# bci02_corrected.net
KiCad netlist of a schematic drawn in Altium Designer
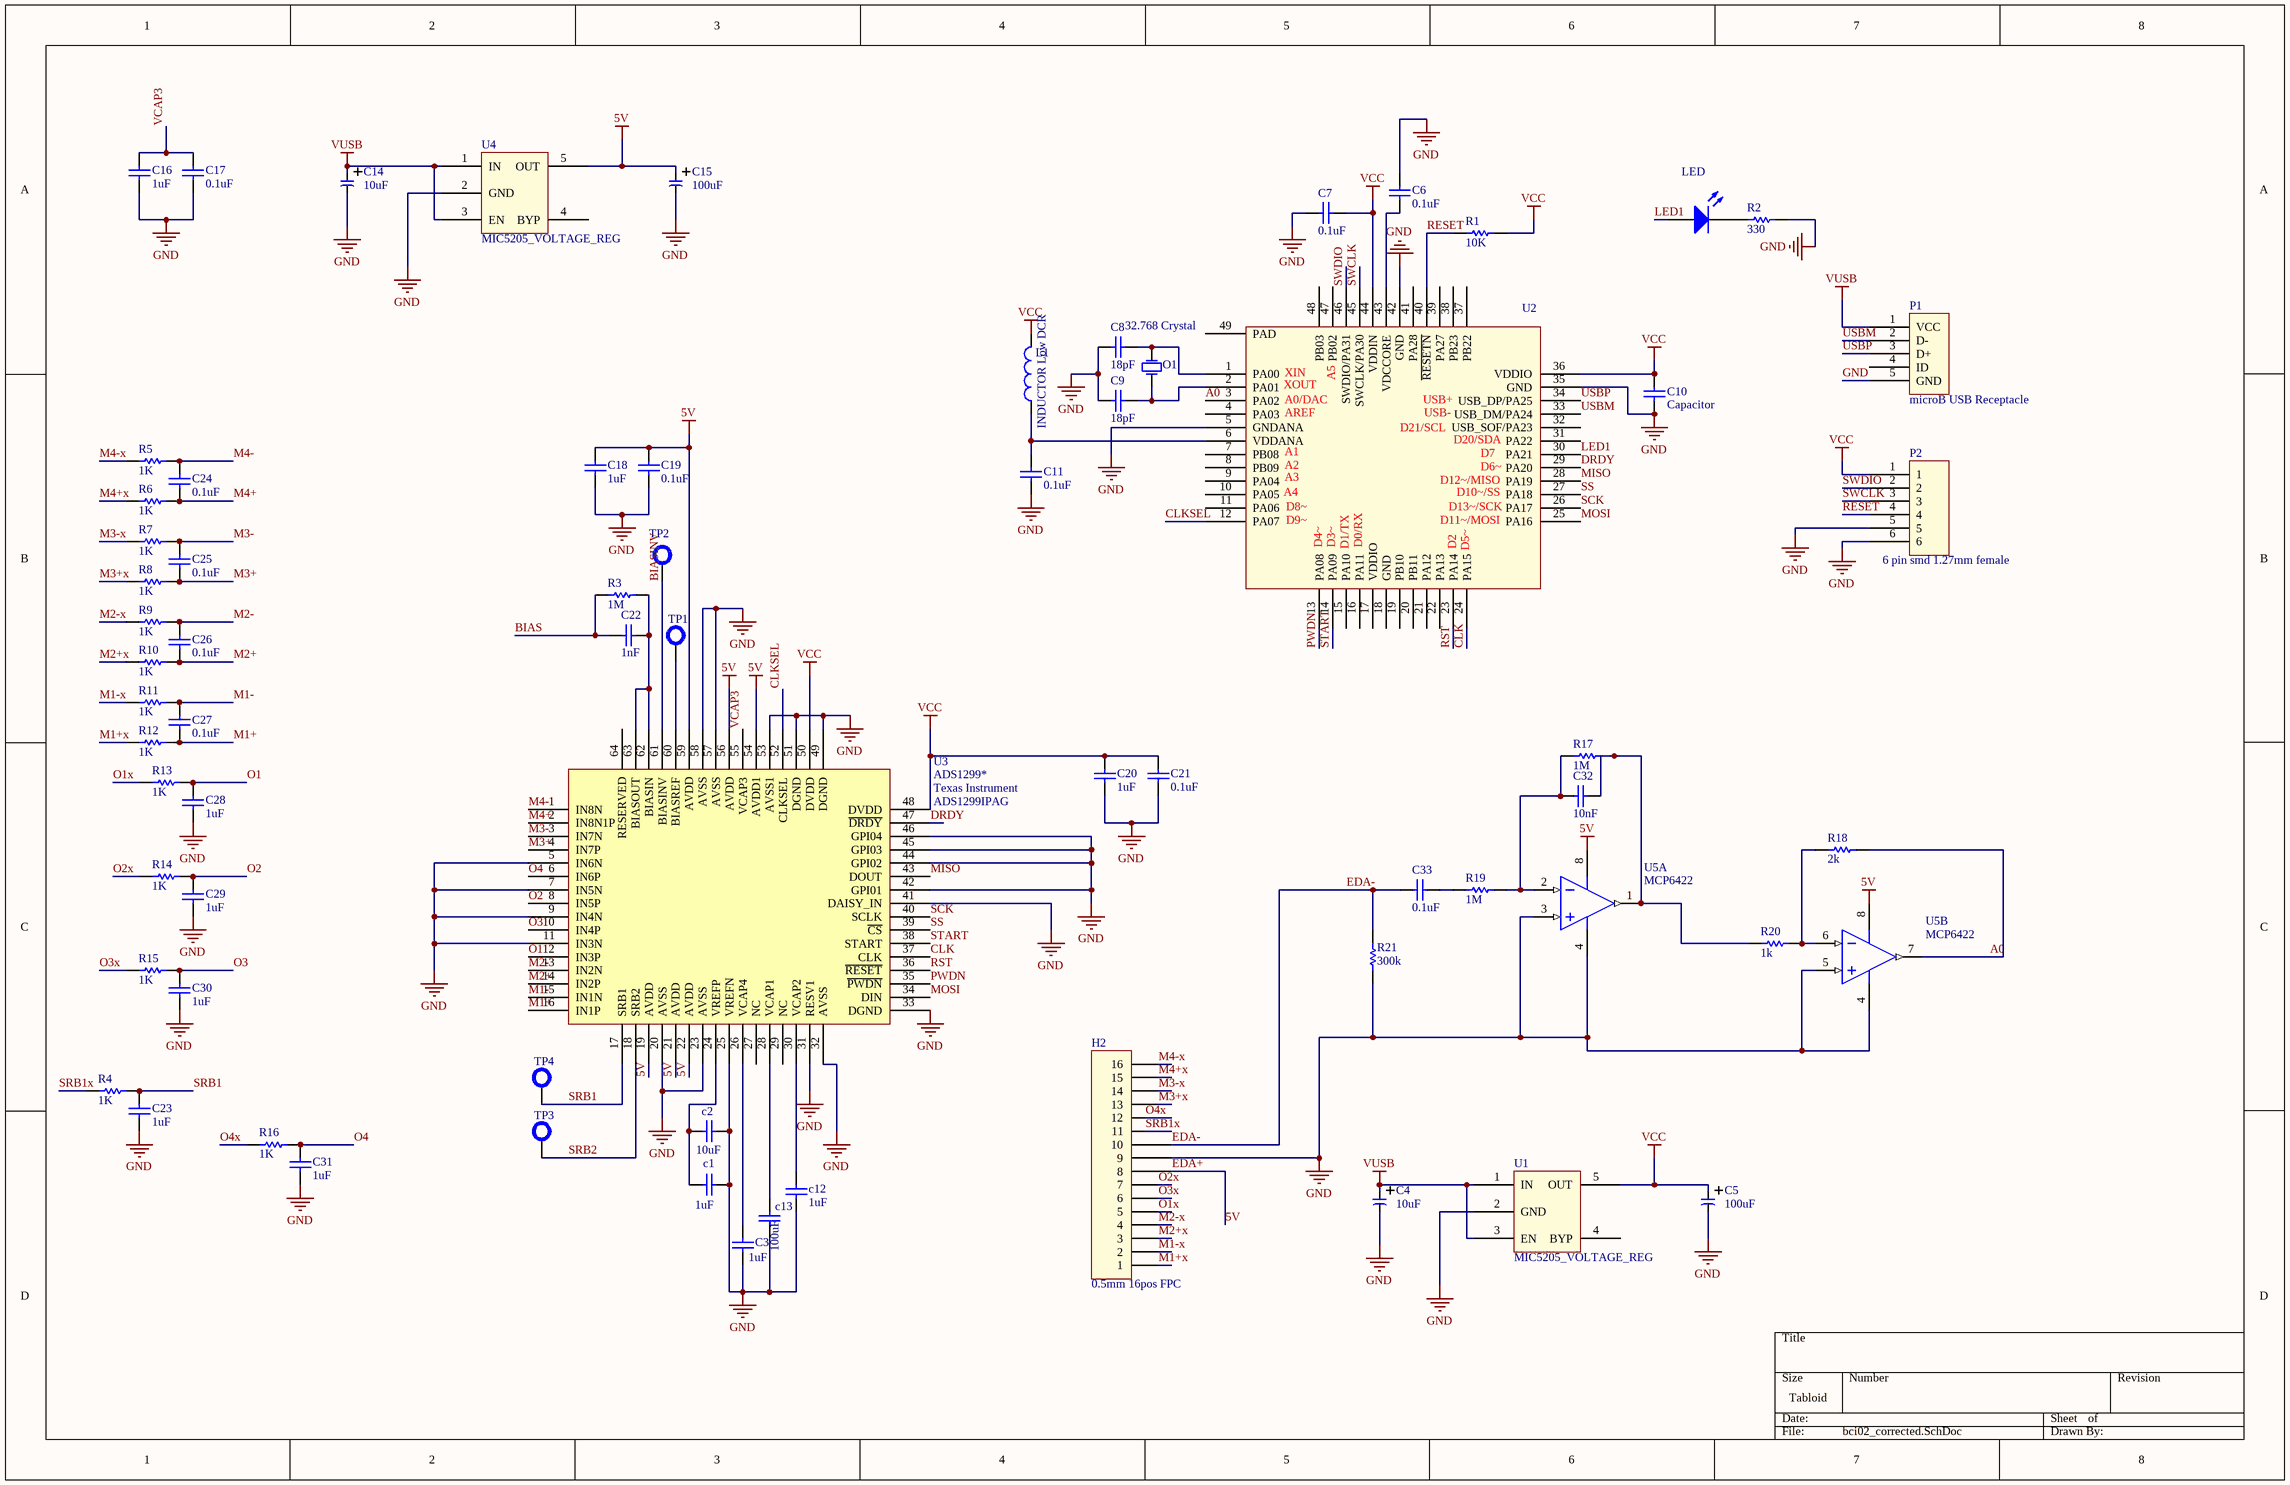
[diagram p0: bci02_corrected.SchDoc]

(export (version "E")
  (design (tool "Eeschema 10.0.6"))
  (components
    (comp (ref "c1")
      (value "1uF")
      (footprint "3-0603")
      (description "SMD Cap 1206")
      (libsource (lib "Artem_Library") (part "Capacitor"))
    )
    (comp (ref "c2")
      (value "10uF")
      (footprint "3-0603")
      (description "SMD Cap 1206")
      (libsource (lib "Artem_Library") (part "Capacitor"))
    )
    (comp (ref "C3")
      (value "1uF")
      (footprint "3-0603")
      (description "SMD Cap 1206")
      (libsource (lib "Artem_Library") (part "Capacitor"))
    )
    (comp (ref "C4")
      (value "10uF")
      (footprint "3-0603")
      (libsource (lib "Artem_Library") (part "Polarized Cap"))
    )
    (comp (ref "C5")
      (value "100uF")
      (footprint "3-0603")
      (libsource (lib "Artem_Library") (part "Polarized Cap"))
    )
    (comp (ref "C6")
      (value "0.1uF")
      (footprint "3-0603")
      (description "SMD Cap 1206")
      (libsource (lib "Artem_Library") (part "Capacitor"))
    )
    (comp (ref "C7")
      (value "0.1uF")
      (footprint "3-0603")
      (description "SMD Cap 1206")
      (libsource (lib "Artem_Library") (part "Capacitor"))
    )
    (comp (ref "C8")
      (value "18pF")
      (footprint "3-0603")
      (description "SMD Cap 1206")
      (libsource (lib "Artem_Library") (part "Capacitor"))
    )
    (comp (ref "C9")
      (value "18pF")
      (footprint "3-0603")
      (description "SMD Cap 1206")
      (libsource (lib "Artem_Library") (part "Capacitor"))
    )
    (comp (ref "C10")
      (value "Capacitor")
      (footprint "3-0603")
      (description "SMD Cap 1206")
      (libsource (lib "Artem_Library") (part "Capacitor"))
    )
    (comp (ref "C11")
      (value "0.1uF")
      (footprint "3-0603")
      (description "SMD Cap 1206")
      (libsource (lib "Artem_Library") (part "Capacitor"))
    )
    (comp (ref "c12")
      (value "1uF")
      (footprint "3-0603")
      (description "SMD Cap 1206")
      (libsource (lib "Artem_Library") (part "Capacitor"))
    )
    (comp (ref "c13")
      (value "100uF")
      (footprint "3-0603")
      (description "SMD Cap 1206")
      (libsource (lib "Artem_Library") (part "Capacitor"))
    )
    (comp (ref "C14")
      (value "10uF")
      (footprint "3-0603")
      (libsource (lib "Artem_Library") (part "Polarized Cap"))
    )
    (comp (ref "C15")
      (value "100uF")
      (footprint "3-0603")
      (libsource (lib "Artem_Library") (part "Polarized Cap"))
    )
    (comp (ref "C16")
      (value "1uF")
      (footprint "3-0603")
      (description "SMD Cap 1206")
      (libsource (lib "Artem_Library") (part "Capacitor"))
    )
    (comp (ref "C17")
      (value "0.1uF")
      (footprint "3-0603")
      (description "SMD Cap 1206")
      (libsource (lib "Artem_Library") (part "Capacitor"))
    )
    (comp (ref "C18")
      (value "1uF")
      (footprint "3-0603")
      (description "SMD Cap 1206")
      (libsource (lib "Artem_Library") (part "Capacitor"))
    )
    (comp (ref "C19")
      (value "0.1uF")
      (footprint "3-0603")
      (description "SMD Cap 1206")
      (libsource (lib "Artem_Library") (part "Capacitor"))
    )
    (comp (ref "C20")
      (value "1uF")
      (footprint "3-0603")
      (description "SMD Cap 1206")
      (libsource (lib "Artem_Library") (part "Capacitor"))
    )
    (comp (ref "C21")
      (value "0.1uF")
      (footprint "3-0603")
      (description "SMD Cap 1206")
      (libsource (lib "Artem_Library") (part "Capacitor"))
    )
    (comp (ref "C22")
      (value "1nF")
      (footprint "3-0603")
      (description "SMD Cap 1206")
      (libsource (lib "Artem_Library") (part "Capacitor"))
    )
    (comp (ref "C23")
      (value "1uF")
      (footprint "0603W")
      (description "SMD Cap 1206")
      (libsource (lib "Artem_Library") (part "Capacitor"))
    )
    (comp (ref "C24")
      (value "0.1uF")
      (footprint "0603W")
      (description "SMD Cap 1206")
      (libsource (lib "Artem_Library") (part "Capacitor"))
    )
    (comp (ref "C25")
      (value "0.1uF")
      (footprint "0603W")
      (description "SMD Cap 1206")
      (libsource (lib "Artem_Library") (part "Capacitor"))
    )
    (comp (ref "C26")
      (value "0.1uF")
      (footprint "0603W")
      (description "SMD Cap 1206")
      (libsource (lib "Artem_Library") (part "Capacitor"))
    )
    (comp (ref "C27")
      (value "0.1uF")
      (footprint "0603W")
      (description "SMD Cap 1206")
      (libsource (lib "Artem_Library") (part "Capacitor"))
    )
    (comp (ref "C28")
      (value "1uF")
      (footprint "0603W")
      (description "SMD Cap 1206")
      (libsource (lib "Artem_Library") (part "Capacitor"))
    )
    (comp (ref "C29")
      (value "1uF")
      (footprint "0603W")
      (description "SMD Cap 1206")
      (libsource (lib "Artem_Library") (part "Capacitor"))
    )
    (comp (ref "C30")
      (value "1uF")
      (footprint "0603W")
      (description "SMD Cap 1206")
      (libsource (lib "Artem_Library") (part "Capacitor"))
    )
    (comp (ref "C31")
      (value "1uF")
      (footprint "0603W")
      (description "SMD Cap 1206")
      (libsource (lib "Artem_Library") (part "Capacitor"))
    )
    (comp (ref "C32")
      (value "10nF")
      (footprint "0603W")
      (description "SMD Cap 1206")
      (libsource (lib "Artem_Library") (part "Capacitor"))
    )
    (comp (ref "C33")
      (value "0.1uF")
      (footprint "0603W")
      (description "SMD Cap 1206")
      (libsource (lib "Artem_Library") (part "Capacitor"))
    )
    (comp (ref "H2")
      (value "0.5mm 16pos FPC")
      (footprint "FPC 16 PIN 0.5mm")
      (libsource (lib "Artem_Library") (part "0.5mm 16pos FPC"))
    )
    (comp (ref "L1")
      (value "INDUCTOR Low DCR")
      (footprint "3-0603")
      (fields (field (name "MANUFACTURER") "NR6028T470M"))
      (libsource (lib "Artem_Library") (part "INDUCTOR Low DCR"))
    )
    (comp (ref "LED1")
      (value "LED")
      (footprint "0603W")
      (description "LED SMD 1206/0603")
      (libsource (lib "Artem_Library") (part "LED"))
    )
    (comp (ref "O1")
      (value "32.768 Crystal")
      (footprint "32.768 Crystal")
      (libsource (lib "Artem_Library") (part "32.768 Crystal"))
    )
    (comp (ref "P1")
      (value "microB USB Receptacle")
      (footprint "MicroB USB Standarad SMT")
      (fields (field (name "MANUFACTURER") "ZX62-B-5PA(11)"))
      (libsource (lib "Artem_Library") (part "microB USB Receptacle"))
    )
    (comp (ref "P2")
      (value "6 pin smd 1.27mm female")
      (footprint "1.27mm smd female")
      (libsource (lib "Artem_Library") (part "6 pin smd 1.27mm female"))
    )
    (comp (ref "R1") (value "10K") (footprint "3-0603") (libsource (lib "Artem_Library") (part "Resistor")))
    (comp (ref "R2") (value "330") (footprint "3-0603") (libsource (lib "Artem_Library") (part "Resistor")))
    (comp (ref "R3") (value "1M") (footprint "3-0603") (libsource (lib "Artem_Library") (part "Resistor")))
    (comp (ref "R4") (value "1K") (footprint "0603W") (libsource (lib "Artem_Library") (part "Resistor")))
    (comp (ref "R5") (value "1K") (footprint "0603W") (libsource (lib "Artem_Library") (part "Resistor")))
    (comp (ref "R6") (value "1K") (footprint "0603W") (libsource (lib "Artem_Library") (part "Resistor")))
    (comp (ref "R7") (value "1K") (footprint "0603W") (libsource (lib "Artem_Library") (part "Resistor")))
    (comp (ref "R8") (value "1K") (footprint "0603W") (libsource (lib "Artem_Library") (part "Resistor")))
    (comp (ref "R9") (value "1K") (footprint "0603W") (libsource (lib "Artem_Library") (part "Resistor")))
    (comp (ref "R10") (value "1K") (footprint "0603W") (libsource (lib "Artem_Library") (part "Resistor")))
    (comp (ref "R11") (value "1K") (footprint "0603W") (libsource (lib "Artem_Library") (part "Resistor")))
    (comp (ref "R12") (value "1K") (footprint "0603W") (libsource (lib "Artem_Library") (part "Resistor")))
    (comp (ref "R13") (value "1K") (footprint "0603W") (libsource (lib "Artem_Library") (part "Resistor")))
    (comp (ref "R14") (value "1K") (footprint "0603W") (libsource (lib "Artem_Library") (part "Resistor")))
    (comp (ref "R15") (value "1K") (footprint "0603W") (libsource (lib "Artem_Library") (part "Resistor")))
    (comp (ref "R16") (value "1K") (footprint "0603W") (libsource (lib "Artem_Library") (part "Resistor")))
    (comp (ref "R17") (value "1M") (footprint "0603W") (libsource (lib "Artem_Library") (part "Resistor")))
    (comp (ref "R18") (value "2k") (footprint "0603W") (libsource (lib "Artem_Library") (part "Resistor")))
    (comp (ref "R19") (value "1M") (footprint "0603W") (libsource (lib "Artem_Library") (part "Resistor")))
    (comp (ref "R20") (value "1k") (footprint "0603W") (libsource (lib "Artem_Library") (part "Resistor")))
    (comp (ref "R21") (value "300k") (footprint "0603W") (libsource (lib "Artem_Library") (part "Resistor")))
    (comp (ref "TP1")
      (value "Test point small")
      (footprint "Test point small")
      (libsource (lib "Artem_Library") (part "Test point small"))
    )
    (comp (ref "TP2")
      (value "Test point small")
      (footprint "Test point small")
      (libsource (lib "Artem_Library") (part "Test point small"))
    )
    (comp (ref "TP3")
      (value "Test point small")
      (footprint "Test point small")
      (libsource (lib "Artem_Library") (part "Test point small"))
    )
    (comp (ref "TP4")
      (value "Test point small")
      (footprint "Test point small")
      (libsource (lib "Artem_Library") (part "Test point small"))
    )
    (comp (ref "U1")
      (value "MIC5205_VOLTAGE_REG")
      (footprint "SOT-23-CT5_M")
      (description "5V LDO SMD")
      (libsource (lib "Artem_Library") (part "MIC5205_VOLTAGE_REG"))
    )
    (comp (ref "U2")
      (value "Component_1")
      (footprint "TQFN48")
      (libsource (lib "Schlib2") (part "Component_1"))
    )
    (comp (ref "U3")
      (value "ADS1299*")
      (footprint "TI-PAG64_M")
      (description "IC AFE 24BIT 16KSPS LN 64TQFP")
      (fields (field (name "MFR 1") "Texas Instrument") (field (name "MFR 1 PN") "ADS1299IPAG"))
      (libsource (lib "CustomComponents") (part "ADS1299"))
    )
    (comp (ref "U4")
      (value "MIC5205_VOLTAGE_REG")
      (footprint "SOT-23-CT5_M")
      (description "5V LDO SMD")
      (libsource (lib "Artem_Library") (part "MIC5205_VOLTAGE_REG"))
    )
    (comp (ref "U5")
      (value "MCP6422")
      (footprint "MSOP-MS8_N")
      (description "4.4 µA/Amplifier, 90 kHz Op Amp")
      (fields
        (field (name "DIGIKEY PART NUMBER") "MCP6422-E/MS-ND")
        (field (name "MANUFACTURER") "Microchip Technology")
      )
      (libsource (lib "Artem_Library") (part "MCP6422"))
    )
  )
  (nets
    (net (code "1") (name "/A0") (class "Default")
      (node (ref "R18") (pin "2") (pinfunction "2_2") (pintype "passive"))
      (node (ref "U2") (pin "3") (pinfunction "PA02_3") (pintype "passive"))
      (node (ref "U5") (pin "7") (pinfunction "VOUTB_7") (pintype "output"))
    )
    (net (code "2") (name "/BIAS") (class "Default")
      (node (ref "C22") (pin "1") (pinfunction "1_1") (pintype "passive"))
      (node (ref "R3") (pin "1") (pinfunction "1_1") (pintype "passive"))
    )
    (net (code "3") (name "/BIASINV") (class "Default")
      (node (ref "TP2") (pin "0") (pinfunction "0_0") (pintype "passive"))
      (node (ref "U3") (pin "61") (pinfunction "BIASINV_61") (pintype "passive"))
    )
    (net (code "4") (name "/CLK") (class "Default")
      (node (ref "U2") (pin "24") (pinfunction "PA15_24") (pintype "passive"))
      (node (ref "U3") (pin "37") (pinfunction "CLK_37") (pintype "passive"))
    )
    (net (code "5") (name "/CLKSEL") (class "Default")
      (node (ref "U2") (pin "12") (pinfunction "PA07_12") (pintype "passive"))
      (node (ref "U3") (pin "52") (pinfunction "CLKSEL_52") (pintype "passive"))
    )
    (net (code "6") (name "/DRDY") (class "Default")
      (node (ref "U2") (pin "29") (pinfunction "PA20_29") (pintype "passive"))
      (node (ref "U3") (pin "47") (pinfunction "~{DRDY}_47") (pintype "passive"))
    )
    (net (code "7") (name "/EDA-") (class "Default")
      (node (ref "C33") (pin "2") (pinfunction "2_2") (pintype "passive"))
      (node (ref "H2") (pin "10") (pinfunction "10_10") (pintype "passive"))
      (node (ref "R21") (pin "2") (pinfunction "2_2") (pintype "passive"))
    )
    (net (code "8") (name "/LED1") (class "Default")
      (node (ref "LED1") (pin "1") (pinfunction "A_1") (pintype "passive"))
      (node (ref "U2") (pin "30") (pinfunction "PA21_30") (pintype "passive"))
    )
    (net (code "9") (name "/M1+") (class "Default")
      (node (ref "C27") (pin "1") (pinfunction "1_1") (pintype "passive"))
      (node (ref "R12") (pin "1") (pinfunction "1_1") (pintype "passive"))
      (node (ref "U3") (pin "16") (pinfunction "IN1P_16") (pintype "passive"))
    )
    (net (code "10") (name "/M1+x") (class "Default")
      (node (ref "H2") (pin "1") (pinfunction "1_1") (pintype "passive"))
      (node (ref "R12") (pin "2") (pinfunction "2_2") (pintype "passive"))
    )
    (net (code "11") (name "/M1-") (class "Default")
      (node (ref "C27") (pin "2") (pinfunction "2_2") (pintype "passive"))
      (node (ref "R11") (pin "1") (pinfunction "1_1") (pintype "passive"))
      (node (ref "U3") (pin "15") (pinfunction "IN1N_15") (pintype "passive"))
    )
    (net (code "12") (name "/M1-x") (class "Default")
      (node (ref "H2") (pin "2") (pinfunction "2_2") (pintype "passive"))
      (node (ref "R11") (pin "2") (pinfunction "2_2") (pintype "passive"))
    )
    (net (code "13") (name "/M2+") (class "Default")
      (node (ref "C26") (pin "1") (pinfunction "1_1") (pintype "passive"))
      (node (ref "R10") (pin "1") (pinfunction "1_1") (pintype "passive"))
      (node (ref "U3") (pin "14") (pinfunction "IN2P_14") (pintype "passive"))
    )
    (net (code "14") (name "/M2+x") (class "Default")
      (node (ref "H2") (pin "3") (pinfunction "3_3") (pintype "passive"))
      (node (ref "R10") (pin "2") (pinfunction "2_2") (pintype "passive"))
    )
    (net (code "15") (name "/M2-") (class "Default")
      (node (ref "C26") (pin "2") (pinfunction "2_2") (pintype "passive"))
      (node (ref "R9") (pin "1") (pinfunction "1_1") (pintype "passive"))
      (node (ref "U3") (pin "13") (pinfunction "IN2N_13") (pintype "passive"))
    )
    (net (code "16") (name "/M2-x") (class "Default")
      (node (ref "H2") (pin "4") (pinfunction "4_4") (pintype "passive"))
      (node (ref "R9") (pin "2") (pinfunction "2_2") (pintype "passive"))
    )
    (net (code "17") (name "/M3+") (class "Default")
      (node (ref "C25") (pin "1") (pinfunction "1_1") (pintype "passive"))
      (node (ref "R8") (pin "1") (pinfunction "1_1") (pintype "passive"))
      (node (ref "U3") (pin "4") (pinfunction "IN7P_4") (pintype "passive"))
    )
    (net (code "18") (name "/M3+x") (class "Default")
      (node (ref "H2") (pin "13") (pinfunction "13_13") (pintype "passive"))
      (node (ref "R8") (pin "2") (pinfunction "2_2") (pintype "passive"))
    )
    (net (code "19") (name "/M3-") (class "Default")
      (node (ref "C25") (pin "2") (pinfunction "2_2") (pintype "passive"))
      (node (ref "R7") (pin "1") (pinfunction "1_1") (pintype "passive"))
      (node (ref "U3") (pin "3") (pinfunction "IN7N_3") (pintype "passive"))
    )
    (net (code "20") (name "/M3-x") (class "Default")
      (node (ref "H2") (pin "14") (pinfunction "14_14") (pintype "passive"))
      (node (ref "R7") (pin "2") (pinfunction "2_2") (pintype "passive"))
    )
    (net (code "21") (name "/M4+") (class "Default")
      (node (ref "C24") (pin "1") (pinfunction "1_1") (pintype "passive"))
      (node (ref "R6") (pin "1") (pinfunction "1_1") (pintype "passive"))
      (node (ref "U3") (pin "2") (pinfunction "IN8N1P_2") (pintype "passive"))
    )
    (net (code "22") (name "/M4+x") (class "Default")
      (node (ref "H2") (pin "15") (pinfunction "15_15") (pintype "passive"))
      (node (ref "R6") (pin "2") (pinfunction "2_2") (pintype "passive"))
    )
    (net (code "23") (name "/M4-") (class "Default")
      (node (ref "C24") (pin "2") (pinfunction "2_2") (pintype "passive"))
      (node (ref "R5") (pin "1") (pinfunction "1_1") (pintype "passive"))
      (node (ref "U3") (pin "1") (pinfunction "IN8N_1") (pintype "passive"))
    )
    (net (code "24") (name "/M4-x") (class "Default")
      (node (ref "H2") (pin "16") (pinfunction "16_16") (pintype "passive"))
      (node (ref "R5") (pin "2") (pinfunction "2_2") (pintype "passive"))
    )
    (net (code "25") (name "/MISO") (class "Default")
      (node (ref "U2") (pin "28") (pinfunction "PA19_28") (pintype "passive"))
      (node (ref "U3") (pin "43") (pinfunction "DOUT_43") (pintype "passive"))
    )
    (net (code "26") (name "/MOSI") (class "Default")
      (node (ref "U2") (pin "25") (pinfunction "PA16_25") (pintype "passive"))
      (node (ref "U3") (pin "34") (pinfunction "DIN_34") (pintype "passive"))
    )
    (net (code "27") (name "/O1") (class "Default")
      (node (ref "C28") (pin "2") (pinfunction "2_2") (pintype "passive"))
      (node (ref "R13") (pin "1") (pinfunction "1_1") (pintype "passive"))
      (node (ref "U3") (pin "12") (pinfunction "IN3P_12") (pintype "passive"))
    )
    (net (code "28") (name "/O1x") (class "Default")
      (node (ref "H2") (pin "5") (pinfunction "5_5") (pintype "passive"))
      (node (ref "R13") (pin "2") (pinfunction "2_2") (pintype "passive"))
    )
    (net (code "29") (name "/O2") (class "Default")
      (node (ref "C29") (pin "2") (pinfunction "2_2") (pintype "passive"))
      (node (ref "R14") (pin "1") (pinfunction "1_1") (pintype "passive"))
      (node (ref "U3") (pin "8") (pinfunction "IN5P_8") (pintype "passive"))
    )
    (net (code "30") (name "/O2x") (class "Default")
      (node (ref "H2") (pin "7") (pinfunction "7_7") (pintype "passive"))
      (node (ref "R14") (pin "2") (pinfunction "2_2") (pintype "passive"))
    )
    (net (code "31") (name "/O3") (class "Default")
      (node (ref "C30") (pin "2") (pinfunction "2_2") (pintype "passive"))
      (node (ref "R15") (pin "1") (pinfunction "1_1") (pintype "passive"))
      (node (ref "U3") (pin "10") (pinfunction "IN4P_10") (pintype "passive"))
    )
    (net (code "32") (name "/O3x") (class "Default")
      (node (ref "H2") (pin "6") (pinfunction "6_6") (pintype "passive"))
      (node (ref "R15") (pin "2") (pinfunction "2_2") (pintype "passive"))
    )
    (net (code "33") (name "/O4") (class "Default")
      (node (ref "C31") (pin "2") (pinfunction "2_2") (pintype "passive"))
      (node (ref "R16") (pin "1") (pinfunction "1_1") (pintype "passive"))
      (node (ref "U3") (pin "6") (pinfunction "IN6P_6") (pintype "passive"))
    )
    (net (code "34") (name "/O4x") (class "Default")
      (node (ref "H2") (pin "12") (pinfunction "12_12") (pintype "passive"))
      (node (ref "R16") (pin "2") (pinfunction "2_2") (pintype "passive"))
    )
    (net (code "35") (name "/PWDN") (class "Default")
      (node (ref "U2") (pin "13") (pinfunction "PA08_13") (pintype "passive"))
      (node (ref "U3") (pin "35") (pinfunction "~{PWDN}_35") (pintype "power_in"))
    )
    (net (code "36") (name "/RESET") (class "Default")
      (node (ref "P2") (pin "4") (pinfunction "4_4") (pintype "passive"))
      (node (ref "R1") (pin "2") (pinfunction "2_2") (pintype "passive"))
      (node (ref "U2") (pin "40") (pinfunction "~{RESETN}_40") (pintype "passive"))
    )
    (net (code "37") (name "/RST") (class "Default")
      (node (ref "U2") (pin "23") (pinfunction "PA14_23") (pintype "passive"))
      (node (ref "U3") (pin "36") (pinfunction "~{RESET}_36") (pintype "passive"))
    )
    (net (code "38") (name "/SCK") (class "Default")
      (node (ref "U2") (pin "26") (pinfunction "PA17_26") (pintype "passive"))
      (node (ref "U3") (pin "40") (pinfunction "SCLK_40") (pintype "passive"))
    )
    (net (code "39") (name "/SRB1") (class "Default")
      (node (ref "C23") (pin "2") (pinfunction "2_2") (pintype "passive"))
      (node (ref "R4") (pin "1") (pinfunction "1_1") (pintype "passive"))
      (node (ref "TP4") (pin "0") (pinfunction "0_0") (pintype "passive"))
      (node (ref "U3") (pin "17") (pinfunction "SRB1_17") (pintype "passive"))
    )
    (net (code "40") (name "/SRB1x") (class "Default")
      (node (ref "H2") (pin "11") (pinfunction "11_11") (pintype "passive"))
      (node (ref "R4") (pin "2") (pinfunction "2_2") (pintype "passive"))
    )
    (net (code "41") (name "/SRB2") (class "Default")
      (node (ref "TP3") (pin "0") (pinfunction "0_0") (pintype "passive"))
      (node (ref "U3") (pin "18") (pinfunction "SRB2_18") (pintype "passive"))
    )
    (net (code "42") (name "/SS") (class "Default")
      (node (ref "U2") (pin "27") (pinfunction "PA18_27") (pintype "passive"))
      (node (ref "U3") (pin "39") (pinfunction "~{CS}_39") (pintype "passive"))
    )
    (net (code "43") (name "/START") (class "Default")
      (node (ref "U2") (pin "14") (pinfunction "PA09_14") (pintype "passive"))
      (node (ref "U3") (pin "38") (pinfunction "START_38") (pintype "passive"))
    )
    (net (code "44") (name "/SWCLK") (class "Default")
      (node (ref "P2") (pin "3") (pinfunction "3_3") (pintype "passive"))
      (node (ref "U2") (pin "45") (pinfunction "SWCLK/PA30_45") (pintype "passive"))
    )
    (net (code "45") (name "/SWDIO") (class "Default")
      (node (ref "P2") (pin "2") (pinfunction "2_2") (pintype "passive"))
      (node (ref "U2") (pin "46") (pinfunction "SWDIO/PA31_46") (pintype "passive"))
    )
    (net (code "46") (name "/USBM") (class "Default")
      (node (ref "P1") (pin "2") (pinfunction "D-_2") (pintype "passive"))
      (node (ref "U2") (pin "33") (pinfunction "USB_DM/PA24_33") (pintype "passive"))
    )
    (net (code "47") (name "/USBP") (class "Default")
      (node (ref "P1") (pin "3") (pinfunction "D+_3") (pintype "passive"))
      (node (ref "U2") (pin "34") (pinfunction "USB_DP/PA25_34") (pintype "passive"))
    )
    (net (code "48") (name "/VCAP3") (class "Default")
      (node (ref "C16") (pin "2") (pinfunction "2_2") (pintype "passive"))
      (node (ref "C17") (pin "2") (pinfunction "2_2") (pintype "passive"))
      (node (ref "U3") (pin "55") (pinfunction "VCAP3_55") (pintype "passive"))
    )
    (net (code "49") (name "5V") (class "Default")
      (node (ref "C15") (pin "1") (pinfunction "1_1") (pintype "passive"))
      (node (ref "C18") (pin "2") (pinfunction "2_2") (pintype "passive"))
      (node (ref "C19") (pin "2") (pinfunction "2_2") (pintype "passive"))
      (node (ref "H2") (pin "8") (pinfunction "8_8") (pintype "passive"))
      (node (ref "U3") (pin "19") (pinfunction "AVDD_19") (pintype "passive"))
      (node (ref "U3") (pin "21") (pinfunction "AVDD_21") (pintype "passive"))
      (node (ref "U3") (pin "22") (pinfunction "AVDD_22") (pintype "passive"))
      (node (ref "U3") (pin "54") (pinfunction "AVDD1_54") (pintype "passive"))
      (node (ref "U3") (pin "56") (pinfunction "AVDD_56") (pintype "passive"))
      (node (ref "U3") (pin "59") (pinfunction "AVDD_59") (pintype "passive"))
      (node (ref "U4") (pin "5") (pinfunction "OUT_5") (pintype "passive"))
      (node (ref "U5") (pin "8") (pinfunction "VDD_8") (pintype "power_in"))
    )
    (net (code "50") (name "GND") (class "Default")
      (node (ref "C10") (pin "1") (pinfunction "1_1") (pintype "passive"))
      (node (ref "C11") (pin "1") (pinfunction "1_1") (pintype "passive"))
      (node (ref "C14") (pin "2") (pinfunction "2_2") (pintype "passive"))
      (node (ref "C15") (pin "2") (pinfunction "2_2") (pintype "passive"))
      (node (ref "C16") (pin "1") (pinfunction "1_1") (pintype "passive"))
      (node (ref "C17") (pin "1") (pinfunction "1_1") (pintype "passive"))
      (node (ref "C18") (pin "1") (pinfunction "1_1") (pintype "passive"))
      (node (ref "C19") (pin "1") (pinfunction "1_1") (pintype "passive"))
      (node (ref "C20") (pin "1") (pinfunction "1_1") (pintype "passive"))
      (node (ref "C21") (pin "1") (pinfunction "1_1") (pintype "passive"))
      (node (ref "C23") (pin "1") (pinfunction "1_1") (pintype "passive"))
      (node (ref "C28") (pin "1") (pinfunction "1_1") (pintype "passive"))
      (node (ref "C29") (pin "1") (pinfunction "1_1") (pintype "passive"))
      (node (ref "C3") (pin "2") (pinfunction "2_2") (pintype "passive"))
      (node (ref "C30") (pin "1") (pinfunction "1_1") (pintype "passive"))
      (node (ref "C31") (pin "1") (pinfunction "1_1") (pintype "passive"))
      (node (ref "C4") (pin "2") (pinfunction "2_2") (pintype "passive"))
      (node (ref "C5") (pin "2") (pinfunction "2_2") (pintype "passive"))
      (node (ref "C6") (pin "2") (pinfunction "2_2") (pintype "passive"))
      (node (ref "C7") (pin "2") (pinfunction "2_2") (pintype "passive"))
      (node (ref "C8") (pin "2") (pinfunction "2_2") (pintype "passive"))
      (node (ref "C9") (pin "2") (pinfunction "2_2") (pintype "passive"))
      (node (ref "H2") (pin "9") (pinfunction "9_9") (pintype "passive"))
      (node (ref "P1") (pin "5") (pinfunction "GND_5") (pintype "passive"))
      (node (ref "P2") (pin "5") (pinfunction "5_5") (pintype "passive"))
      (node (ref "P2") (pin "6") (pinfunction "6_6") (pintype "passive"))
      (node (ref "R2") (pin "1") (pinfunction "1_1") (pintype "passive"))
      (node (ref "R21") (pin "1") (pinfunction "1_1") (pintype "passive"))
      (node (ref "U1") (pin "2") (pinfunction "GND_2") (pintype "passive"))
      (node (ref "U2") (pin "35") (pinfunction "GND_35") (pintype "passive"))
      (node (ref "U2") (pin "42") (pinfunction "GND_42") (pintype "passive"))
      (node (ref "U2") (pin "5") (pinfunction "GNDANA_5") (pintype "passive"))
      (node (ref "U3") (pin "11") (pinfunction "IN3N_11") (pintype "passive"))
      (node (ref "U3") (pin "20") (pinfunction "AVSS_20") (pintype "passive"))
      (node (ref "U3") (pin "23") (pinfunction "AVSS_23") (pintype "passive"))
      (node (ref "U3") (pin "25") (pinfunction "VREFN_25") (pintype "passive"))
      (node (ref "U3") (pin "31") (pinfunction "RESV1_31") (pintype "passive"))
      (node (ref "U3") (pin "32") (pinfunction "AVSS_32") (pintype "passive"))
      (node (ref "U3") (pin "33") (pinfunction "DGND_33") (pintype "passive"))
      (node (ref "U3") (pin "41") (pinfunction "DAISY_IN_41") (pintype "passive"))
      (node (ref "U3") (pin "42") (pinfunction "GPI01_42") (pintype "passive"))
      (node (ref "U3") (pin "44") (pinfunction "GPI02_44") (pintype "passive"))
      (node (ref "U3") (pin "45") (pinfunction "GPI03_45") (pintype "passive"))
      (node (ref "U3") (pin "46") (pinfunction "GPI04_46") (pintype "passive"))
      (node (ref "U3") (pin "49") (pinfunction "DGND_49") (pintype "passive"))
      (node (ref "U3") (pin "5") (pinfunction "IN6N_5") (pintype "passive"))
      (node (ref "U3") (pin "51") (pinfunction "DGND_51") (pintype "passive"))
      (node (ref "U3") (pin "53") (pinfunction "AVSS1_53") (pintype "passive"))
      (node (ref "U3") (pin "57") (pinfunction "AVSS_57") (pintype "passive"))
      (node (ref "U3") (pin "58") (pinfunction "AVSS_58") (pintype "passive"))
      (node (ref "U3") (pin "7") (pinfunction "IN5N_7") (pintype "passive"))
      (node (ref "U3") (pin "9") (pinfunction "IN4N_9") (pintype "passive"))
      (node (ref "U4") (pin "2") (pinfunction "GND_2") (pintype "passive"))
      (node (ref "U5") (pin "3") (pinfunction "VINA+_3") (pintype "input"))
      (node (ref "U5") (pin "4") (pinfunction "VSS_4") (pintype "power_in"))
      (node (ref "U5") (pin "5") (pinfunction "VINB+_5") (pintype "input"))
      (node (ref "c1") (pin "2") (pinfunction "2_2") (pintype "passive"))
      (node (ref "c12") (pin "2") (pinfunction "2_2") (pintype "passive"))
      (node (ref "c13") (pin "2") (pinfunction "2_2") (pintype "passive"))
      (node (ref "c2") (pin "2") (pinfunction "2_2") (pintype "passive"))
    )
    (net (code "51") (name "Net-(C33-Pad1)") (class "Default")
      (node (ref "C33") (pin "1") (pinfunction "1_1") (pintype "passive"))
      (node (ref "R19") (pin "1") (pinfunction "1_1") (pintype "passive"))
    )
    (net (code "52") (name "Net-(LED1-K)") (class "Default")
      (node (ref "LED1") (pin "2") (pinfunction "K_2") (pintype "passive"))
      (node (ref "R2") (pin "2") (pinfunction "2_2") (pintype "passive"))
    )
    (net (code "53") (name "Net-(U2-PA00)") (class "Default")
      (node (ref "C8") (pin "1") (pinfunction "1_1") (pintype "passive"))
      (node (ref "O1") (pin "1") (pinfunction "1_1") (pintype "passive"))
      (node (ref "U2") (pin "1") (pinfunction "PA00_1") (pintype "passive"))
    )
    (net (code "54") (name "Net-(U2-PA01)") (class "Default")
      (node (ref "C9") (pin "1") (pinfunction "1_1") (pintype "passive"))
      (node (ref "O1") (pin "2") (pinfunction "2_2") (pintype "passive"))
      (node (ref "U2") (pin "2") (pinfunction "PA01_2") (pintype "passive"))
    )
    (net (code "55") (name "Net-(U2-VDCCORE)") (class "Default")
      (node (ref "C6") (pin "1") (pinfunction "1_1") (pintype "passive"))
      (node (ref "U2") (pin "43") (pinfunction "VDCCORE_43") (pintype "passive"))
    )
    (net (code "56") (name "Net-(U2-VDDANA)") (class "Default")
      (node (ref "C11") (pin "2") (pinfunction "2_2") (pintype "passive"))
      (node (ref "L1") (pin "1") (pinfunction "1_1") (pintype "passive"))
      (node (ref "U2") (pin "6") (pinfunction "VDDANA_6") (pintype "passive"))
    )
    (net (code "57") (name "Net-(U3-BIASIN)") (class "Default")
      (node (ref "C22") (pin "2") (pinfunction "2_2") (pintype "passive"))
      (node (ref "R3") (pin "2") (pinfunction "2_2") (pintype "passive"))
      (node (ref "U3") (pin "62") (pinfunction "BIASIN_62") (pintype "passive"))
      (node (ref "U3") (pin "63") (pinfunction "BIASOUT_63") (pintype "passive"))
    )
    (net (code "58") (name "Net-(U3-BIASREF)") (class "Default")
      (node (ref "TP1") (pin "0") (pinfunction "0_0") (pintype "passive"))
      (node (ref "U3") (pin "60") (pinfunction "BIASREF_60") (pintype "passive"))
    )
    (net (code "59") (name "Net-(U3-VCAP1)") (class "Default")
      (node (ref "U3") (pin "28") (pinfunction "VCAP1_28") (pintype "passive"))
      (node (ref "c13") (pin "1") (pinfunction "1_1") (pintype "passive"))
    )
    (net (code "60") (name "Net-(U3-VCAP2)") (class "Default")
      (node (ref "U3") (pin "30") (pinfunction "VCAP2_30") (pintype "passive"))
      (node (ref "c12") (pin "1") (pinfunction "1_1") (pintype "passive"))
    )
    (net (code "61") (name "Net-(U3-VCAP4)") (class "Default")
      (node (ref "C3") (pin "1") (pinfunction "1_1") (pintype "passive"))
      (node (ref "U3") (pin "26") (pinfunction "VCAP4_26") (pintype "passive"))
    )
    (net (code "62") (name "Net-(U3-VREFP)") (class "Default")
      (node (ref "U3") (pin "24") (pinfunction "VREFP_24") (pintype "passive"))
      (node (ref "c1") (pin "1") (pinfunction "1_1") (pintype "passive"))
      (node (ref "c2") (pin "1") (pinfunction "1_1") (pintype "passive"))
    )
    (net (code "63") (name "Net-(U5A-VINA-)") (class "Default")
      (node (ref "C32") (pin "2") (pinfunction "2_2") (pintype "passive"))
      (node (ref "R17") (pin "1") (pinfunction "1_1") (pintype "passive"))
      (node (ref "R19") (pin "2") (pinfunction "2_2") (pintype "passive"))
      (node (ref "U5") (pin "2") (pinfunction "VINA-_2") (pintype "input"))
    )
    (net (code "64") (name "Net-(U5A-VOUTA)") (class "Default")
      (node (ref "C32") (pin "1") (pinfunction "1_1") (pintype "passive"))
      (node (ref "R17") (pin "2") (pinfunction "2_2") (pintype "passive"))
      (node (ref "R20") (pin "1") (pinfunction "1_1") (pintype "passive"))
      (node (ref "U5") (pin "1") (pinfunction "VOUTA_1") (pintype "output"))
    )
    (net (code "65") (name "Net-(U5B-VINB-)") (class "Default")
      (node (ref "R18") (pin "1") (pinfunction "1_1") (pintype "passive"))
      (node (ref "R20") (pin "2") (pinfunction "2_2") (pintype "passive"))
      (node (ref "U5") (pin "6") (pinfunction "VINB-_6") (pintype "input"))
    )
    (net (code "66") (name "VCC") (class "Default")
      (node (ref "C10") (pin "2") (pinfunction "2_2") (pintype "passive"))
      (node (ref "C20") (pin "2") (pinfunction "2_2") (pintype "passive"))
      (node (ref "C21") (pin "2") (pinfunction "2_2") (pintype "passive"))
      (node (ref "C5") (pin "1") (pinfunction "1_1") (pintype "passive"))
      (node (ref "C7") (pin "1") (pinfunction "1_1") (pintype "passive"))
      (node (ref "L1") (pin "2") (pinfunction "2_2") (pintype "passive"))
      (node (ref "P2") (pin "1") (pinfunction "1_1") (pintype "passive"))
      (node (ref "R1") (pin "1") (pinfunction "1_1") (pintype "passive"))
      (node (ref "U1") (pin "5") (pinfunction "OUT_5") (pintype "passive"))
      (node (ref "U2") (pin "36") (pinfunction "VDDIO_36") (pintype "passive"))
      (node (ref "U2") (pin "44") (pinfunction "VDDIN_44") (pintype "passive"))
      (node (ref "U3") (pin "48") (pinfunction "DVDD_48") (pintype "passive"))
      (node (ref "U3") (pin "50") (pinfunction "DVDD_50") (pintype "passive"))
    )
    (net (code "67") (name "VUSB") (class "Default")
      (node (ref "C14") (pin "1") (pinfunction "1_1") (pintype "passive"))
      (node (ref "C4") (pin "1") (pinfunction "1_1") (pintype "passive"))
      (node (ref "P1") (pin "1") (pinfunction "VCC_1") (pintype "passive"))
      (node (ref "U1") (pin "1") (pinfunction "IN_1") (pintype "passive"))
      (node (ref "U1") (pin "3") (pinfunction "EN_3") (pintype "passive"))
      (node (ref "U4") (pin "1") (pinfunction "IN_1") (pintype "passive"))
      (node (ref "U4") (pin "3") (pinfunction "EN_3") (pintype "passive"))
    )
    (net (code "68") (name "unconnected-(P1-ID-Pad4)") (class "Default")
      (node (ref "P1") (pin "4") (pinfunction "ID_4") (pintype "passive"))
    )
    (net (code "69") (name "unconnected-(U1-BYP-Pad4)") (class "Default")
      (node (ref "U1") (pin "4") (pinfunction "BYP_4") (pintype "passive"))
    )
    (net (code "70") (name "unconnected-(U2-GND-Pad18)") (class "Default")
      (node (ref "U2") (pin "18") (pinfunction "GND_18") (pintype "passive"))
    )
    (net (code "71") (name "unconnected-(U2-PA03-Pad4)") (class "Default")
      (node (ref "U2") (pin "4") (pinfunction "PA03_4") (pintype "passive"))
    )
    (net (code "72") (name "unconnected-(U2-PA04-Pad9)") (class "Default")
      (node (ref "U2") (pin "9") (pinfunction "PA04_9") (pintype "passive"))
    )
    (net (code "73") (name "unconnected-(U2-PA05-Pad10)") (class "Default")
      (node (ref "U2") (pin "10") (pinfunction "PA05_10") (pintype "passive"))
    )
    (net (code "74") (name "unconnected-(U2-PA06-Pad11)") (class "Default")
      (node (ref "U2") (pin "11") (pinfunction "PA06_11") (pintype "passive"))
    )
    (net (code "75") (name "unconnected-(U2-PA10-Pad15)") (class "Default")
      (node (ref "U2") (pin "15") (pinfunction "PA10_15") (pintype "passive"))
    )
    (net (code "76") (name "unconnected-(U2-PA11-Pad16)") (class "Default")
      (node (ref "U2") (pin "16") (pinfunction "PA11_16") (pintype "passive"))
    )
    (net (code "77") (name "unconnected-(U2-PA12-Pad21)") (class "Default")
      (node (ref "U2") (pin "21") (pinfunction "PA12_21") (pintype "passive"))
    )
    (net (code "78") (name "unconnected-(U2-PA13-Pad22)") (class "Default")
      (node (ref "U2") (pin "22") (pinfunction "PA13_22") (pintype "passive"))
    )
    (net (code "79") (name "unconnected-(U2-PA22-Pad31)") (class "Default")
      (node (ref "U2") (pin "31") (pinfunction "PA22_31") (pintype "passive"))
    )
    (net (code "80") (name "unconnected-(U2-PA27-Pad39)") (class "Default")
      (node (ref "U2") (pin "39") (pinfunction "PA27_39") (pintype "passive"))
    )
    (net (code "81") (name "unconnected-(U2-PA28-Pad41)") (class "Default")
      (node (ref "U2") (pin "41") (pinfunction "PA28_41") (pintype "passive"))
    )
    (net (code "82") (name "unconnected-(U2-PAD-Pad49)") (class "Default")
      (node (ref "U2") (pin "49") (pinfunction "PAD_49") (pintype "passive"))
    )
    (net (code "83") (name "unconnected-(U2-PB02-Pad47)") (class "Default")
      (node (ref "U2") (pin "47") (pinfunction "PB02_47") (pintype "passive"))
    )
    (net (code "84") (name "unconnected-(U2-PB03-Pad48)") (class "Default")
      (node (ref "U2") (pin "48") (pinfunction "PB03_48") (pintype "passive"))
    )
    (net (code "85") (name "unconnected-(U2-PB08-Pad7)") (class "Default")
      (node (ref "U2") (pin "7") (pinfunction "PB08_7") (pintype "passive"))
    )
    (net (code "86") (name "unconnected-(U2-PB09-Pad8)") (class "Default")
      (node (ref "U2") (pin "8") (pinfunction "PB09_8") (pintype "passive"))
    )
    (net (code "87") (name "unconnected-(U2-PB10-Pad19)") (class "Default")
      (node (ref "U2") (pin "19") (pinfunction "PB10_19") (pintype "passive"))
    )
    (net (code "88") (name "unconnected-(U2-PB11-Pad20)") (class "Default")
      (node (ref "U2") (pin "20") (pinfunction "PB11_20") (pintype "passive"))
    )
    (net (code "89") (name "unconnected-(U2-PB22-Pad37)") (class "Default")
      (node (ref "U2") (pin "37") (pinfunction "PB22_37") (pintype "passive"))
    )
    (net (code "90") (name "unconnected-(U2-PB23-Pad38)") (class "Default")
      (node (ref "U2") (pin "38") (pinfunction "PB23_38") (pintype "passive"))
    )
    (net (code "91") (name "unconnected-(U2-USB_SOF{slash}PA23-Pad32)") (class "Default")
      (node (ref "U2") (pin "32") (pinfunction "USB_SOF/PA23_32") (pintype "passive"))
    )
    (net (code "92") (name "unconnected-(U2-VDDIO-Pad17)") (class "Default")
      (node (ref "U2") (pin "17") (pinfunction "VDDIO_17") (pintype "passive"))
    )
    (net (code "93") (name "unconnected-(U3-NC-Pad27)") (class "Default")
      (node (ref "U3") (pin "27") (pinfunction "NC_27") (pintype "passive"))
    )
    (net (code "94") (name "unconnected-(U3-NC-Pad29)") (class "Default")
      (node (ref "U3") (pin "29") (pinfunction "NC_29") (pintype "passive"))
    )
    (net (code "95") (name "unconnected-(U3-RESERVED-Pad64)") (class "Default")
      (node (ref "U3") (pin "64") (pinfunction "RESERVED_64") (pintype "passive"))
    )
    (net (code "96") (name "unconnected-(U4-BYP-Pad4)") (class "Default")
      (node (ref "U4") (pin "4") (pinfunction "BYP_4") (pintype "passive"))
    )
  )
)
